# Sheet_1_2020-09-21_08-20-19.net
KiCad netlist of a schematic drawn in Altium Designer
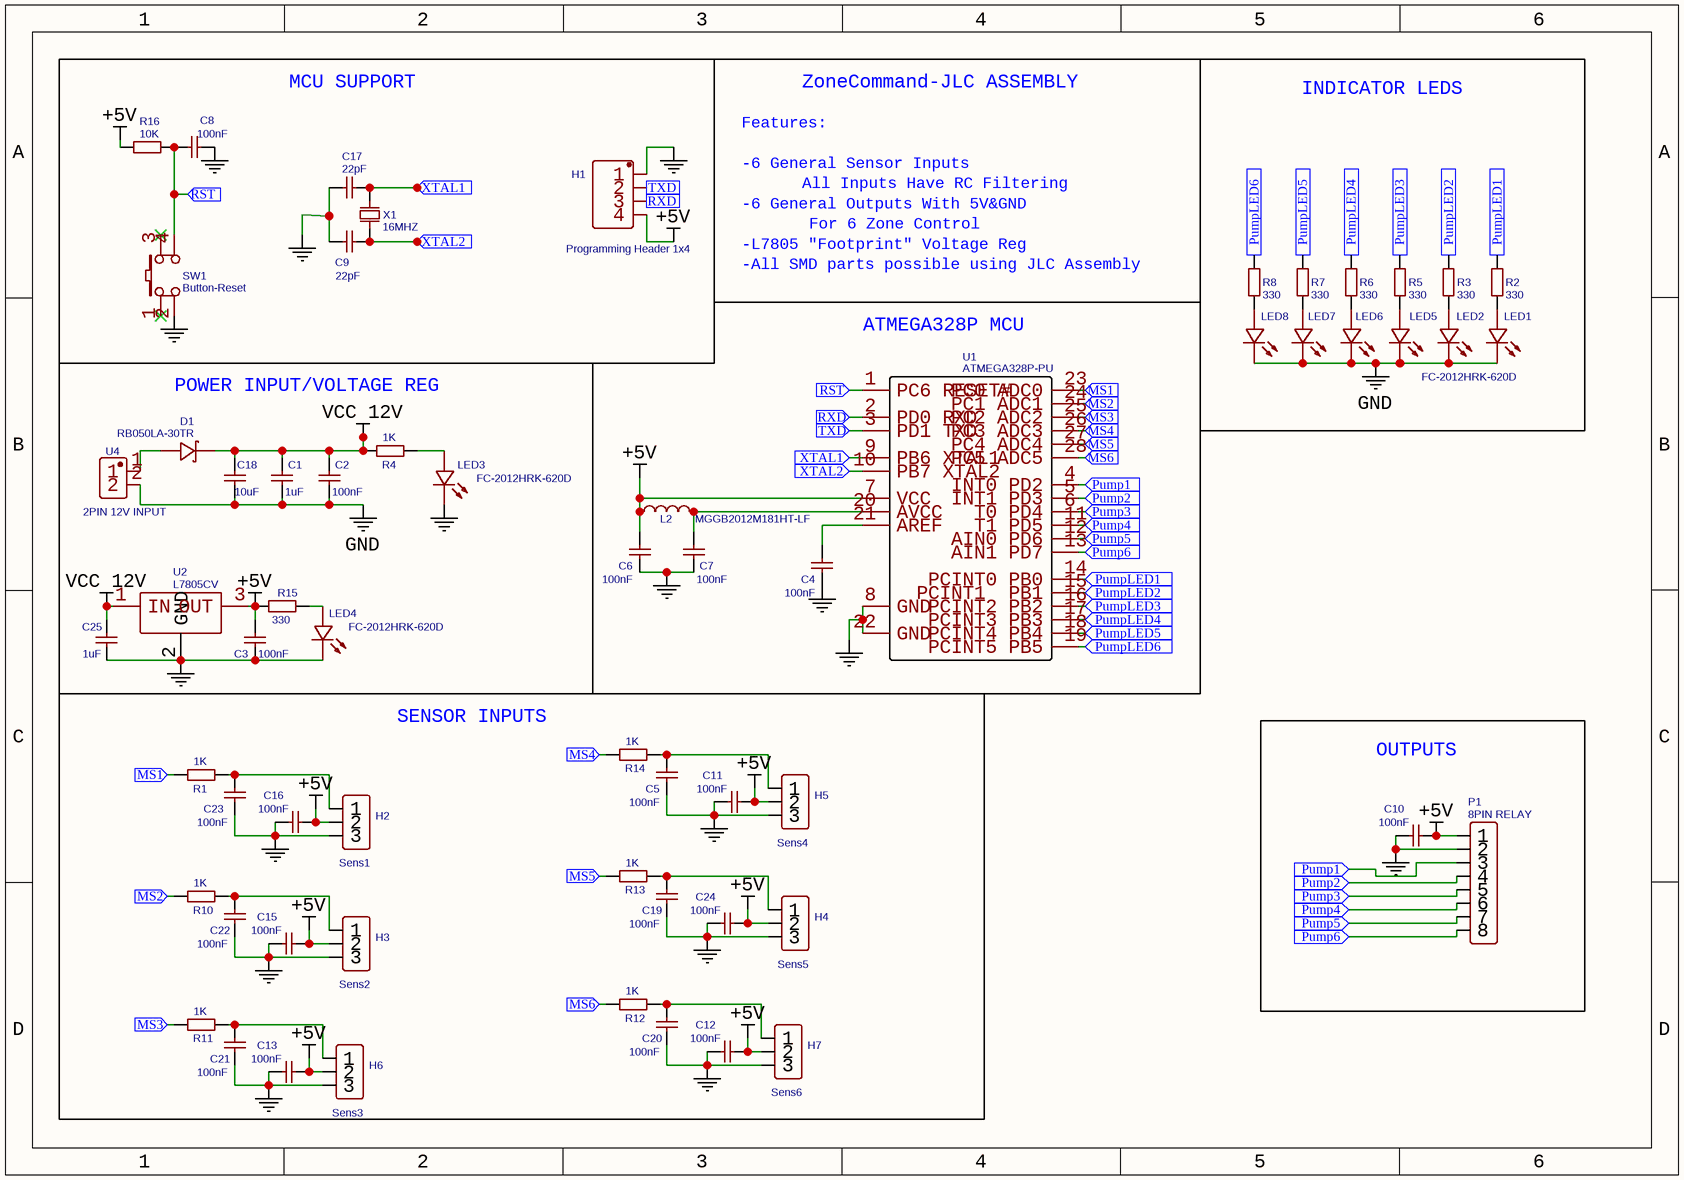
[diagram p0: Sheet_1_2020-09-21_08-20-19.schdoc]

(export (version "E")
  (design (tool "Eeschema 10.0.6"))
  (components
    (comp (ref "C1")
      (value "1uF")
      (fields
        (field (name "BOM_MANUFACTURER PART") "CL21B105KBFNNNE")
        (field (name "BOM_SUPPLIER PART") "C28323")
      )
      (libsource (lib "altium-import") (part "root_1_1uF_"))
    )
    (comp (ref "C2")
      (value "100nF")
      (fields
        (field (name "BOM_MANUFACTURER PART") "CC0805KRX7R9BB104")
        (field (name "BOM_SUPPLIER PART") "C49678")
      )
      (libsource (lib "altium-import") (part "root_3_100nF_"))
    )
    (comp (ref "C3")
      (value "100nF")
      (fields
        (field (name "BOM_MANUFACTURER PART") "CC0805KRX7R9BB104")
        (field (name "BOM_SUPPLIER PART") "C49678")
      )
      (libsource (lib "altium-import") (part "root_3_100nF_"))
    )
    (comp (ref "C4")
      (value "100nF")
      (fields
        (field (name "BOM_MANUFACTURER PART") "CC0805KRX7R9BB104")
        (field (name "BOM_SUPPLIER PART") "C49678")
      )
      (libsource (lib "altium-import") (part "root_3_100nF_"))
    )
    (comp (ref "C5")
      (value "100nF")
      (fields
        (field (name "BOM_MANUFACTURER PART") "CC0805KRX7R9BB104")
        (field (name "BOM_SUPPLIER PART") "C49678")
      )
      (libsource (lib "altium-import") (part "root_3_100nF_"))
    )
    (comp (ref "C6")
      (value "100nF")
      (fields
        (field (name "BOM_MANUFACTURER PART") "CC0805KRX7R9BB104")
        (field (name "BOM_SUPPLIER PART") "C49678")
      )
      (libsource (lib "altium-import") (part "root_3_100nF_"))
    )
    (comp (ref "C7")
      (value "100nF")
      (fields
        (field (name "BOM_MANUFACTURER PART") "CC0805KRX7R9BB104")
        (field (name "BOM_SUPPLIER PART") "C49678")
      )
      (libsource (lib "altium-import") (part "root_3_100nF_"))
    )
    (comp (ref "C8")
      (value "100nF")
      (fields
        (field (name "BOM_MANUFACTURER PART") "CC0805KRX7R9BB104")
        (field (name "BOM_SUPPLIER PART") "C49678")
      )
      (libsource (lib "altium-import") (part "root_0_100nF_"))
    )
    (comp (ref "C9")
      (value "22pF")
      (fields
        (field (name "BOM_MANUFACTURER PART") "CL21C220JBANNNC")
        (field (name "BOM_SUPPLIER PART") "C1804")
      )
      (libsource (lib "altium-import") (part "root_0_22pF_"))
    )
    (comp (ref "C10")
      (value "100nF")
      (fields
        (field (name "BOM_MANUFACTURER PART") "CC0805KRX7R9BB104")
        (field (name "BOM_SUPPLIER PART") "C49678")
      )
      (libsource (lib "altium-import") (part "root_0_100nF_"))
    )
    (comp (ref "C11")
      (value "100nF")
      (fields
        (field (name "BOM_MANUFACTURER PART") "CC0805KRX7R9BB104")
        (field (name "BOM_SUPPLIER PART") "C49678")
      )
      (libsource (lib "altium-import") (part "root_0_100nF_"))
    )
    (comp (ref "C12")
      (value "100nF")
      (fields
        (field (name "BOM_MANUFACTURER PART") "CC0805KRX7R9BB104")
        (field (name "BOM_SUPPLIER PART") "C49678")
      )
      (libsource (lib "altium-import") (part "root_0_100nF_"))
    )
    (comp (ref "C13")
      (value "100nF")
      (fields
        (field (name "BOM_MANUFACTURER PART") "CC0805KRX7R9BB104")
        (field (name "BOM_SUPPLIER PART") "C49678")
      )
      (libsource (lib "altium-import") (part "root_0_100nF_"))
    )
    (comp (ref "C15")
      (value "100nF")
      (fields
        (field (name "BOM_MANUFACTURER PART") "CC0805KRX7R9BB104")
        (field (name "BOM_SUPPLIER PART") "C49678")
      )
      (libsource (lib "altium-import") (part "root_0_100nF_"))
    )
    (comp (ref "C16")
      (value "100nF")
      (fields
        (field (name "BOM_MANUFACTURER PART") "CC0805KRX7R9BB104")
        (field (name "BOM_SUPPLIER PART") "C49678")
      )
      (libsource (lib "altium-import") (part "root_0_100nF_"))
    )
    (comp (ref "C17")
      (value "22pF")
      (fields
        (field (name "BOM_MANUFACTURER PART") "CL21C220JBANNNC")
        (field (name "BOM_SUPPLIER PART") "C1804")
      )
      (libsource (lib "altium-import") (part "root_0_22pF_"))
    )
    (comp (ref "C18")
      (value "10uF")
      (fields
        (field (name "BOM_MANUFACTURER PART") "CL21A106KAYNNNE")
        (field (name "BOM_SUPPLIER PART") "C15850")
      )
      (libsource (lib "altium-import") (part "root_3_10uF_"))
    )
    (comp (ref "C19")
      (value "100nF")
      (fields
        (field (name "BOM_MANUFACTURER PART") "CC0805KRX7R9BB104")
        (field (name "BOM_SUPPLIER PART") "C49678")
      )
      (libsource (lib "altium-import") (part "root_3_100nF_"))
    )
    (comp (ref "C20")
      (value "100nF")
      (fields
        (field (name "BOM_MANUFACTURER PART") "CC0805KRX7R9BB104")
        (field (name "BOM_SUPPLIER PART") "C49678")
      )
      (libsource (lib "altium-import") (part "root_3_100nF_"))
    )
    (comp (ref "C21")
      (value "100nF")
      (fields
        (field (name "BOM_MANUFACTURER PART") "CC0805KRX7R9BB104")
        (field (name "BOM_SUPPLIER PART") "C49678")
      )
      (libsource (lib "altium-import") (part "root_3_100nF_"))
    )
    (comp (ref "C22")
      (value "100nF")
      (fields
        (field (name "BOM_MANUFACTURER PART") "CC0805KRX7R9BB104")
        (field (name "BOM_SUPPLIER PART") "C49678")
      )
      (libsource (lib "altium-import") (part "root_3_100nF_"))
    )
    (comp (ref "C23")
      (value "100nF")
      (fields
        (field (name "BOM_MANUFACTURER PART") "CC0805KRX7R9BB104")
        (field (name "BOM_SUPPLIER PART") "C49678")
      )
      (libsource (lib "altium-import") (part "root_3_100nF_"))
    )
    (comp (ref "C24")
      (value "100nF")
      (fields
        (field (name "BOM_MANUFACTURER PART") "CC0805KRX7R9BB104")
        (field (name "BOM_SUPPLIER PART") "C49678")
      )
      (libsource (lib "altium-import") (part "root_0_100nF_"))
    )
    (comp (ref "C25")
      (value "1uF")
      (fields
        (field (name "BOM_MANUFACTURER PART") "CL21B105KBFNNNE")
        (field (name "BOM_SUPPLIER PART") "C28323")
      )
      (libsource (lib "altium-import") (part "root_1_1uF_"))
    )
    (comp (ref "D1")
      (value "RB050LA-30TR")
      (fields (field (name "BOM_SUPPLIER PART") "C162057") (field (name "CONTRIBUTOR") "LCSC"))
      (libsource (lib "altium-import") (part "root_0_RB050LA-30TR_"))
    )
    (comp (ref "H1")
      (value "Programming Header 1x4")
      (fields
        (field (name "BOM_MANUFACTURER PART") "210S-1*4P L=11.6MMGold-plated black")
        (field (name "BOM_SUPPLIER PART") "C124378")
        (field (name "CONTRIBUTOR") "LCSC")
      )
      (libsource (lib "altium-import") (part "root_0_Programming Header 1x4_"))
    )
    (comp (ref "H2")
      (value "Sens1")
      (fields
        (field (name "BOM_MANUFACTURER PART") "Header2.54mm 1*3P")
        (field (name "BOM_SUPPLIER PART") "C49257")
      )
      (libsource (lib "altium-import") (part "root_0_Sens1_"))
    )
    (comp (ref "H3")
      (value "Sens2")
      (fields
        (field (name "BOM_MANUFACTURER PART") "Header2.54mm 1*3P")
        (field (name "BOM_SUPPLIER PART") "C49257")
      )
      (libsource (lib "altium-import") (part "root_0_Sens2_"))
    )
    (comp (ref "H4")
      (value "Sens5")
      (fields
        (field (name "BOM_MANUFACTURER PART") "Header2.54mm 1*3P")
        (field (name "BOM_SUPPLIER PART") "C49257")
      )
      (libsource (lib "altium-import") (part "root_0_Sens5_"))
    )
    (comp (ref "H5")
      (value "Sens4")
      (fields
        (field (name "BOM_MANUFACTURER PART") "Header2.54mm 1*3P")
        (field (name "BOM_SUPPLIER PART") "C49257")
      )
      (libsource (lib "altium-import") (part "root_0_Sens4_"))
    )
    (comp (ref "H6")
      (value "Sens3")
      (fields
        (field (name "BOM_MANUFACTURER PART") "Header2.54mm 1*3P")
        (field (name "BOM_SUPPLIER PART") "C49257")
      )
      (libsource (lib "altium-import") (part "root_0_Sens3_"))
    )
    (comp (ref "H7")
      (value "Sens6")
      (fields
        (field (name "BOM_MANUFACTURER PART") "Header2.54mm 1*3P")
        (field (name "BOM_SUPPLIER PART") "C49257")
      )
      (libsource (lib "altium-import") (part "root_0_Sens6_"))
    )
    (comp (ref "L2")
      (value "MGGB2012M181HT-LF")
      (fields (field (name "BOM_SUPPLIER PART") "C486339") (field (name "CONTRIBUTOR") "LCSC"))
      (libsource (lib "altium-import") (part "root_0_MGGB2012M181HT-LF_"))
    )
    (comp (ref "LED1")
      (value "FC-2012HRK-620D")
      (fields (field (name "BOM_SUPPLIER PART") "C84256"))
      (libsource (lib "altium-import") (part "root_1_FC-2012HRK-620D_"))
    )
    (comp (ref "LED2")
      (value "FC-2012HRK-620D")
      (fields (field (name "BOM_SUPPLIER PART") "C84256"))
      (libsource (lib "altium-import") (part "root_1_FC-2012HRK-620D_"))
    )
    (comp (ref "LED3")
      (value "FC-2012HRK-620D")
      (fields (field (name "BOM_SUPPLIER PART") "C84256"))
      (libsource (lib "altium-import") (part "root_1_FC-2012HRK-620D_"))
    )
    (comp (ref "LED4")
      (value "FC-2012HRK-620D")
      (fields (field (name "BOM_SUPPLIER PART") "C84256"))
      (libsource (lib "altium-import") (part "root_1_FC-2012HRK-620D_"))
    )
    (comp (ref "LED5")
      (value "FC-2012HRK-620D")
      (fields (field (name "BOM_SUPPLIER PART") "C84256"))
      (libsource (lib "altium-import") (part "root_1_FC-2012HRK-620D_"))
    )
    (comp (ref "LED6")
      (value "FC-2012HRK-620D")
      (fields (field (name "BOM_SUPPLIER PART") "C84256"))
      (libsource (lib "altium-import") (part "root_1_FC-2012HRK-620D_"))
    )
    (comp (ref "LED7")
      (value "FC-2012HRK-620D")
      (fields (field (name "BOM_SUPPLIER PART") "C84256"))
      (libsource (lib "altium-import") (part "root_1_FC-2012HRK-620D_"))
    )
    (comp (ref "LED8")
      (value "FC-2012HRK-620D")
      (fields (field (name "BOM_SUPPLIER PART") "C84256"))
      (libsource (lib "altium-import") (part "root_1_FC-2012HRK-620D_"))
    )
    (comp (ref "P1")
      (value "8PIN RELAY")
      (fields
        (field (name "BOM_MANUFACTURER PART") "Female headerHDR1X8-2.54")
        (field (name "BOM_SUPPLIER PART") "C27438")
      )
      (libsource (lib "altium-import") (part "root_0_8PIN RELAY_"))
    )
    (comp (ref "R1")
      (value "1K")
      (fields
        (field (name "BOM_MANUFACTURER PART") "0805W8F1001T5E")
        (field (name "BOM_SUPPLIER PART") "C17513")
      )
      (libsource (lib "altium-import") (part "root_0_1K_"))
    )
    (comp (ref "R2")
      (value "330")
      (fields
        (field (name "BOM_MANUFACTURER PART") "0805W8F3300T5E")
        (field (name "BOM_SUPPLIER PART") "C17630")
      )
      (libsource (lib "altium-import") (part "root_1_330_"))
    )
    (comp (ref "R3")
      (value "330")
      (fields
        (field (name "BOM_MANUFACTURER PART") "0805W8F3300T5E")
        (field (name "BOM_SUPPLIER PART") "C17630")
      )
      (libsource (lib "altium-import") (part "root_1_330_"))
    )
    (comp (ref "R4")
      (value "1K")
      (fields
        (field (name "BOM_MANUFACTURER PART") "0805W8F1001T5E")
        (field (name "BOM_SUPPLIER PART") "C17513")
      )
      (libsource (lib "altium-import") (part "root_0_1K_"))
    )
    (comp (ref "R5")
      (value "330")
      (fields
        (field (name "BOM_MANUFACTURER PART") "0805W8F3300T5E")
        (field (name "BOM_SUPPLIER PART") "C17630")
      )
      (libsource (lib "altium-import") (part "root_1_330_"))
    )
    (comp (ref "R6")
      (value "330")
      (fields
        (field (name "BOM_MANUFACTURER PART") "0805W8F3300T5E")
        (field (name "BOM_SUPPLIER PART") "C17630")
      )
      (libsource (lib "altium-import") (part "root_1_330_"))
    )
    (comp (ref "R7")
      (value "330")
      (fields
        (field (name "BOM_MANUFACTURER PART") "0805W8F3300T5E")
        (field (name "BOM_SUPPLIER PART") "C17630")
      )
      (libsource (lib "altium-import") (part "root_1_330_"))
    )
    (comp (ref "R8")
      (value "330")
      (fields
        (field (name "BOM_MANUFACTURER PART") "0805W8F3300T5E")
        (field (name "BOM_SUPPLIER PART") "C17630")
      )
      (libsource (lib "altium-import") (part "root_1_330_"))
    )
    (comp (ref "R10")
      (value "1K")
      (fields
        (field (name "BOM_MANUFACTURER PART") "0805W8F1001T5E")
        (field (name "BOM_SUPPLIER PART") "C17513")
      )
      (libsource (lib "altium-import") (part "root_0_1K_"))
    )
    (comp (ref "R11")
      (value "1K")
      (fields
        (field (name "BOM_MANUFACTURER PART") "0805W8F1001T5E")
        (field (name "BOM_SUPPLIER PART") "C17513")
      )
      (libsource (lib "altium-import") (part "root_0_1K_"))
    )
    (comp (ref "R12")
      (value "1K")
      (fields
        (field (name "BOM_MANUFACTURER PART") "0805W8F1001T5E")
        (field (name "BOM_SUPPLIER PART") "C17513")
      )
      (libsource (lib "altium-import") (part "root_0_1K_"))
    )
    (comp (ref "R13")
      (value "1K")
      (fields
        (field (name "BOM_MANUFACTURER PART") "0805W8F1001T5E")
        (field (name "BOM_SUPPLIER PART") "C17513")
      )
      (libsource (lib "altium-import") (part "root_0_1K_"))
    )
    (comp (ref "R14")
      (value "1K")
      (fields
        (field (name "BOM_MANUFACTURER PART") "0805W8F1001T5E")
        (field (name "BOM_SUPPLIER PART") "C17513")
      )
      (libsource (lib "altium-import") (part "root_0_1K_"))
    )
    (comp (ref "R15")
      (value "330")
      (fields
        (field (name "BOM_MANUFACTURER PART") "0805W8F3300T5E")
        (field (name "BOM_SUPPLIER PART") "C17630")
      )
      (libsource (lib "altium-import") (part "root_0_330_"))
    )
    (comp (ref "R16")
      (value "10K")
      (fields
        (field (name "BOM_MANUFACTURER PART") "0805W8F1002T5E")
        (field (name "BOM_SUPPLIER PART") "C17414")
      )
      (libsource (lib "altium-import") (part "root_0_10K_"))
    )
    (comp (ref "SW1")
      (value "Button-Reset")
      (fields
        (field (name "BOM_SUPPLIER PART") "C71836")
        (field (name "BOM_MANUFACTURER PART") "Switch,6*6*6Plastic head,260G, 0.25mm,Straight line")
      )
      (libsource (lib "altium-import") (part "root_1_Button-Reset_"))
    )
    (comp (ref "U1")
      (value "ATMEGA328P-PU")
      (fields (field (name "BOM_SUPPLIER PART") "C33901") (field (name "CONTRIBUTOR") "LCSC"))
      (libsource (lib "altium-import") (part "root_0_ATMEGA328P-PU_"))
    )
    (comp (ref "U2")
      (value "L7805CV")
      (fields (field (name "BOM_SUPPLIER PART") "C111887"))
      (libsource (lib "altium-import") (part "root_0_L7805CV_"))
    )
    (comp (ref "U4")
      (value "2PIN 12V INPUT")
      (fields
        (field (name "BOM_SUPPLIER PART") "C691859")
        (field (name "BOM_MANUFACTURER PART") "DG500-5.08-02P-14-00A(H)")
        (field (name "CONTRIBUTOR") "LCSC")
      )
      (libsource (lib "altium-import") (part "root_0_2PIN 12V INPUT_"))
    )
    (comp (ref "X1")
      (value "16MHZ")
      (fields
        (field (name "BOM_SUPPLIER PART") "C389708")
        (field (name "BOM_MANUFACTURER PART") "5S0-1600A1620-00")
        (field (name "CONTRIBUTOR") "LCSC")
      )
      (libsource (lib "altium-import") (part "root_3_16MHZ_"))
    )
  )
  (nets
    (net (code "1") (name "+5V") (class "Default")
      (node (ref "C10") (pin "2") (pinfunction "2_2") (pintype "passive"))
      (node (ref "C11") (pin "2") (pinfunction "2_2") (pintype "passive"))
      (node (ref "C12") (pin "2") (pinfunction "2_2") (pintype "passive"))
      (node (ref "C13") (pin "2") (pinfunction "2_2") (pintype "passive"))
      (node (ref "C15") (pin "2") (pinfunction "2_2") (pintype "passive"))
      (node (ref "C16") (pin "2") (pinfunction "2_2") (pintype "passive"))
      (node (ref "C24") (pin "2") (pinfunction "2_2") (pintype "passive"))
      (node (ref "C3") (pin "1") (pinfunction "1_1") (pintype "passive"))
      (node (ref "C6") (pin "1") (pinfunction "1_1") (pintype "passive"))
      (node (ref "H1") (pin "4") (pinfunction "4_4") (pintype "passive"))
      (node (ref "H2") (pin "2") (pinfunction "2_2") (pintype "passive"))
      (node (ref "H3") (pin "2") (pinfunction "2_2") (pintype "passive"))
      (node (ref "H4") (pin "2") (pinfunction "2_2") (pintype "passive"))
      (node (ref "H5") (pin "2") (pinfunction "2_2") (pintype "passive"))
      (node (ref "H6") (pin "2") (pinfunction "2_2") (pintype "passive"))
      (node (ref "H7") (pin "2") (pinfunction "2_2") (pintype "passive"))
      (node (ref "L2") (pin "1") (pinfunction "1_1") (pintype "passive"))
      (node (ref "P1") (pin "1") (pinfunction "1_1") (pintype "passive"))
      (node (ref "R15") (pin "1") (pinfunction "1_1") (pintype "passive"))
      (node (ref "R16") (pin "1") (pinfunction "1_1") (pintype "passive"))
      (node (ref "U1") (pin "7") (pinfunction "VCC_7") (pintype "passive"))
      (node (ref "U2") (pin "3") (pinfunction "OUT_3") (pintype "passive"))
    )
    (net (code "2") (name "/MS1") (class "Default")
      (node (ref "R1") (pin "1") (pinfunction "1_1") (pintype "passive"))
      (node (ref "U1") (pin "23") (pinfunction "PC0_ADC0_23") (pintype "passive"))
    )
    (net (code "3") (name "/MS2") (class "Default")
      (node (ref "R10") (pin "1") (pinfunction "1_1") (pintype "passive"))
      (node (ref "U1") (pin "24") (pinfunction "PC1_ADC1_24") (pintype "passive"))
    )
    (net (code "4") (name "/MS3") (class "Default")
      (node (ref "R11") (pin "1") (pinfunction "1_1") (pintype "passive"))
      (node (ref "U1") (pin "25") (pinfunction "PC2_ADC2_25") (pintype "passive"))
    )
    (net (code "5") (name "/MS4") (class "Default")
      (node (ref "R14") (pin "1") (pinfunction "1_1") (pintype "passive"))
      (node (ref "U1") (pin "26") (pinfunction "PC3_ADC3_26") (pintype "passive"))
    )
    (net (code "6") (name "/MS5") (class "Default")
      (node (ref "R13") (pin "1") (pinfunction "1_1") (pintype "passive"))
      (node (ref "U1") (pin "27") (pinfunction "PC4_ADC4_27") (pintype "passive"))
    )
    (net (code "7") (name "/MS6") (class "Default")
      (node (ref "R12") (pin "1") (pinfunction "1_1") (pintype "passive"))
      (node (ref "U1") (pin "28") (pinfunction "PC5_ADC5_28") (pintype "passive"))
    )
    (net (code "8") (name "/Pump1") (class "Default")
      (node (ref "P1") (pin "3") (pinfunction "3_3") (pintype "passive"))
      (node (ref "U1") (pin "4") (pinfunction "INT0_PD2_4") (pintype "passive"))
    )
    (net (code "9") (name "/Pump2") (class "Default")
      (node (ref "P1") (pin "4") (pinfunction "4_4") (pintype "passive"))
      (node (ref "U1") (pin "5") (pinfunction "INT1_PD3_5") (pintype "passive"))
    )
    (net (code "10") (name "/Pump3") (class "Default")
      (node (ref "P1") (pin "5") (pinfunction "5_5") (pintype "passive"))
      (node (ref "U1") (pin "6") (pinfunction "T0_PD4_6") (pintype "passive"))
    )
    (net (code "11") (name "/Pump4") (class "Default")
      (node (ref "P1") (pin "6") (pinfunction "6_6") (pintype "passive"))
      (node (ref "U1") (pin "11") (pinfunction "T1_PD5_11") (pintype "passive"))
    )
    (net (code "12") (name "/Pump5") (class "Default")
      (node (ref "P1") (pin "7") (pinfunction "7_7") (pintype "passive"))
      (node (ref "U1") (pin "12") (pinfunction "AIN0_PD6_12") (pintype "passive"))
    )
    (net (code "13") (name "/Pump6") (class "Default")
      (node (ref "P1") (pin "8") (pinfunction "8_8") (pintype "passive"))
      (node (ref "U1") (pin "13") (pinfunction "AIN1_PD7_13") (pintype "passive"))
    )
    (net (code "14") (name "/PumpLED1") (class "Default")
      (node (ref "R2") (pin "2") (pinfunction "2_2") (pintype "passive"))
      (node (ref "U1") (pin "14") (pinfunction "PCINT0_PB0_14") (pintype "passive"))
    )
    (net (code "15") (name "/PumpLED2") (class "Default")
      (node (ref "R3") (pin "2") (pinfunction "2_2") (pintype "passive"))
      (node (ref "U1") (pin "15") (pinfunction "PCINT1__PB1_15") (pintype "passive"))
    )
    (net (code "16") (name "/PumpLED3") (class "Default")
      (node (ref "R5") (pin "2") (pinfunction "2_2") (pintype "passive"))
      (node (ref "U1") (pin "16") (pinfunction "PCINT2_PB2_16") (pintype "passive"))
    )
    (net (code "17") (name "/PumpLED4") (class "Default")
      (node (ref "R6") (pin "2") (pinfunction "2_2") (pintype "passive"))
      (node (ref "U1") (pin "17") (pinfunction "PCINT3_PB3_17") (pintype "passive"))
    )
    (net (code "18") (name "/PumpLED5") (class "Default")
      (node (ref "R7") (pin "2") (pinfunction "2_2") (pintype "passive"))
      (node (ref "U1") (pin "18") (pinfunction "PCINT4_PB4_18") (pintype "passive"))
    )
    (net (code "19") (name "/PumpLED6") (class "Default")
      (node (ref "R8") (pin "2") (pinfunction "2_2") (pintype "passive"))
      (node (ref "U1") (pin "19") (pinfunction "PCINT5_PB5_19") (pintype "passive"))
    )
    (net (code "20") (name "/RST") (class "Default")
      (node (ref "C8") (pin "1") (pinfunction "1_1") (pintype "passive"))
      (node (ref "R16") (pin "2") (pinfunction "2_2") (pintype "passive"))
      (node (ref "SW1") (pin "4") (pinfunction "4_4") (pintype "passive"))
      (node (ref "U1") (pin "1") (pinfunction "PC6_RESET#_1") (pintype "passive"))
    )
    (net (code "21") (name "/RXD") (class "Default")
      (node (ref "H1") (pin "3") (pinfunction "3_3") (pintype "passive"))
      (node (ref "U1") (pin "2") (pinfunction "PD0_RXD_2") (pintype "passive"))
    )
    (net (code "22") (name "/TXD") (class "Default")
      (node (ref "H1") (pin "2") (pinfunction "2_2") (pintype "passive"))
      (node (ref "U1") (pin "3") (pinfunction "PD1_TXD_3") (pintype "passive"))
    )
    (net (code "23") (name "/XTAL1") (class "Default")
      (node (ref "C17") (pin "2") (pinfunction "2_2") (pintype "passive"))
      (node (ref "U1") (pin "9") (pinfunction "PB6_XTAL1_9") (pintype "passive"))
      (node (ref "X1") (pin "1") (pinfunction "OSC1_1") (pintype "passive"))
    )
    (net (code "24") (name "/XTAL2") (class "Default")
      (node (ref "C9") (pin "2") (pinfunction "2_2") (pintype "passive"))
      (node (ref "U1") (pin "10") (pinfunction "PB7_XTAL2_10") (pintype "passive"))
      (node (ref "X1") (pin "2") (pinfunction "OSC2_2") (pintype "passive"))
    )
    (net (code "25") (name "GND") (class "Default")
      (node (ref "C1") (pin "1") (pinfunction "1_1") (pintype "passive"))
      (node (ref "C10") (pin "1") (pinfunction "1_1") (pintype "passive"))
      (node (ref "C11") (pin "1") (pinfunction "1_1") (pintype "passive"))
      (node (ref "C12") (pin "1") (pinfunction "1_1") (pintype "passive"))
      (node (ref "C13") (pin "1") (pinfunction "1_1") (pintype "passive"))
      (node (ref "C15") (pin "1") (pinfunction "1_1") (pintype "passive"))
      (node (ref "C16") (pin "1") (pinfunction "1_1") (pintype "passive"))
      (node (ref "C17") (pin "1") (pinfunction "1_1") (pintype "passive"))
      (node (ref "C18") (pin "2") (pinfunction "2_2") (pintype "passive"))
      (node (ref "C19") (pin "2") (pinfunction "2_2") (pintype "passive"))
      (node (ref "C2") (pin "2") (pinfunction "2_2") (pintype "passive"))
      (node (ref "C20") (pin "2") (pinfunction "2_2") (pintype "passive"))
      (node (ref "C21") (pin "2") (pinfunction "2_2") (pintype "passive"))
      (node (ref "C22") (pin "2") (pinfunction "2_2") (pintype "passive"))
      (node (ref "C23") (pin "2") (pinfunction "2_2") (pintype "passive"))
      (node (ref "C24") (pin "1") (pinfunction "1_1") (pintype "passive"))
      (node (ref "C25") (pin "1") (pinfunction "1_1") (pintype "passive"))
      (node (ref "C3") (pin "2") (pinfunction "2_2") (pintype "passive"))
      (node (ref "C4") (pin "2") (pinfunction "2_2") (pintype "passive"))
      (node (ref "C5") (pin "2") (pinfunction "2_2") (pintype "passive"))
      (node (ref "C6") (pin "2") (pinfunction "2_2") (pintype "passive"))
      (node (ref "C7") (pin "2") (pinfunction "2_2") (pintype "passive"))
      (node (ref "C8") (pin "2") (pinfunction "2_2") (pintype "passive"))
      (node (ref "C9") (pin "1") (pinfunction "1_1") (pintype "passive"))
      (node (ref "H1") (pin "1") (pinfunction "1_1") (pintype "passive"))
      (node (ref "H2") (pin "3") (pinfunction "3_3") (pintype "passive"))
      (node (ref "H3") (pin "3") (pinfunction "3_3") (pintype "passive"))
      (node (ref "H4") (pin "3") (pinfunction "3_3") (pintype "passive"))
      (node (ref "H5") (pin "3") (pinfunction "3_3") (pintype "passive"))
      (node (ref "H6") (pin "3") (pinfunction "3_3") (pintype "passive"))
      (node (ref "H7") (pin "3") (pinfunction "3_3") (pintype "passive"))
      (node (ref "LED1") (pin "1") (pinfunction "-_1") (pintype "passive"))
      (node (ref "LED2") (pin "1") (pinfunction "-_1") (pintype "passive"))
      (node (ref "LED3") (pin "1") (pinfunction "-_1") (pintype "passive"))
      (node (ref "LED4") (pin "1") (pinfunction "-_1") (pintype "passive"))
      (node (ref "LED5") (pin "1") (pinfunction "-_1") (pintype "passive"))
      (node (ref "LED6") (pin "1") (pinfunction "-_1") (pintype "passive"))
      (node (ref "LED7") (pin "1") (pinfunction "-_1") (pintype "passive"))
      (node (ref "LED8") (pin "1") (pinfunction "-_1") (pintype "passive"))
      (node (ref "P1") (pin "2") (pinfunction "2_2") (pintype "passive"))
      (node (ref "SW1") (pin "2") (pinfunction "2_2") (pintype "passive"))
      (node (ref "U1") (pin "22") (pinfunction "GND_22") (pintype "passive"))
      (node (ref "U1") (pin "8") (pinfunction "GND_8") (pintype "passive"))
      (node (ref "U2") (pin "2") (pinfunction "GND_2") (pintype "passive"))
      (node (ref "U4") (pin "2") (pinfunction "2_2") (pintype "passive"))
    )
    (net (code "26") (name "Net-(C5-Pad1)") (class "Default")
      (node (ref "C5") (pin "1") (pinfunction "1_1") (pintype "passive"))
      (node (ref "H5") (pin "1") (pinfunction "1_1") (pintype "passive"))
      (node (ref "R14") (pin "2") (pinfunction "2_2") (pintype "passive"))
    )
    (net (code "27") (name "Net-(C19-Pad1)") (class "Default")
      (node (ref "C19") (pin "1") (pinfunction "1_1") (pintype "passive"))
      (node (ref "H4") (pin "1") (pinfunction "1_1") (pintype "passive"))
      (node (ref "R13") (pin "2") (pinfunction "2_2") (pintype "passive"))
    )
    (net (code "28") (name "Net-(C20-Pad1)") (class "Default")
      (node (ref "C20") (pin "1") (pinfunction "1_1") (pintype "passive"))
      (node (ref "H7") (pin "1") (pinfunction "1_1") (pintype "passive"))
      (node (ref "R12") (pin "2") (pinfunction "2_2") (pintype "passive"))
    )
    (net (code "29") (name "Net-(C21-Pad1)") (class "Default")
      (node (ref "C21") (pin "1") (pinfunction "1_1") (pintype "passive"))
      (node (ref "H6") (pin "1") (pinfunction "1_1") (pintype "passive"))
      (node (ref "R11") (pin "2") (pinfunction "2_2") (pintype "passive"))
    )
    (net (code "30") (name "Net-(C22-Pad1)") (class "Default")
      (node (ref "C22") (pin "1") (pinfunction "1_1") (pintype "passive"))
      (node (ref "H3") (pin "1") (pinfunction "1_1") (pintype "passive"))
      (node (ref "R10") (pin "2") (pinfunction "2_2") (pintype "passive"))
    )
    (net (code "31") (name "Net-(C23-Pad1)") (class "Default")
      (node (ref "C23") (pin "1") (pinfunction "1_1") (pintype "passive"))
      (node (ref "H2") (pin "1") (pinfunction "1_1") (pintype "passive"))
      (node (ref "R1") (pin "2") (pinfunction "2_2") (pintype "passive"))
    )
    (net (code "32") (name "Net-(D1-A)") (class "Default")
      (node (ref "D1") (pin "2") (pinfunction "A_2") (pintype "passive"))
      (node (ref "U4") (pin "1") (pinfunction "1_1") (pintype "passive"))
    )
    (net (code "33") (name "Net-(LED1-+)") (class "Default")
      (node (ref "LED1") (pin "2") (pinfunction "+_2") (pintype "passive"))
      (node (ref "R2") (pin "1") (pinfunction "1_1") (pintype "passive"))
    )
    (net (code "34") (name "Net-(LED2-+)") (class "Default")
      (node (ref "LED2") (pin "2") (pinfunction "+_2") (pintype "passive"))
      (node (ref "R3") (pin "1") (pinfunction "1_1") (pintype "passive"))
    )
    (net (code "35") (name "Net-(LED3-+)") (class "Default")
      (node (ref "LED3") (pin "2") (pinfunction "+_2") (pintype "passive"))
      (node (ref "R4") (pin "2") (pinfunction "2_2") (pintype "passive"))
    )
    (net (code "36") (name "Net-(LED4-+)") (class "Default")
      (node (ref "LED4") (pin "2") (pinfunction "+_2") (pintype "passive"))
      (node (ref "R15") (pin "2") (pinfunction "2_2") (pintype "passive"))
    )
    (net (code "37") (name "Net-(LED5-+)") (class "Default")
      (node (ref "LED5") (pin "2") (pinfunction "+_2") (pintype "passive"))
      (node (ref "R5") (pin "1") (pinfunction "1_1") (pintype "passive"))
    )
    (net (code "38") (name "Net-(LED6-+)") (class "Default")
      (node (ref "LED6") (pin "2") (pinfunction "+_2") (pintype "passive"))
      (node (ref "R6") (pin "1") (pinfunction "1_1") (pintype "passive"))
    )
    (net (code "39") (name "Net-(LED7-+)") (class "Default")
      (node (ref "LED7") (pin "2") (pinfunction "+_2") (pintype "passive"))
      (node (ref "R7") (pin "1") (pinfunction "1_1") (pintype "passive"))
    )
    (net (code "40") (name "Net-(LED8-+)") (class "Default")
      (node (ref "LED8") (pin "2") (pinfunction "+_2") (pintype "passive"))
      (node (ref "R8") (pin "1") (pinfunction "1_1") (pintype "passive"))
    )
    (net (code "41") (name "Net-(U1-AREF)") (class "Default")
      (node (ref "C4") (pin "1") (pinfunction "1_1") (pintype "passive"))
      (node (ref "U1") (pin "21") (pinfunction "AREF_21") (pintype "passive"))
    )
    (net (code "42") (name "Net-(U1-AVCC)") (class "Default")
      (node (ref "C7") (pin "1") (pinfunction "1_1") (pintype "passive"))
      (node (ref "L2") (pin "2") (pinfunction "2_2") (pintype "passive"))
      (node (ref "U1") (pin "20") (pinfunction "AVCC_20") (pintype "passive"))
    )
    (net (code "43") (name "VCC 12V") (class "Default")
      (node (ref "C1") (pin "2") (pinfunction "2_2") (pintype "passive"))
      (node (ref "C18") (pin "1") (pinfunction "1_1") (pintype "passive"))
      (node (ref "C2") (pin "1") (pinfunction "1_1") (pintype "passive"))
      (node (ref "C25") (pin "2") (pinfunction "2_2") (pintype "passive"))
      (node (ref "D1") (pin "1") (pinfunction "K_1") (pintype "passive"))
      (node (ref "R4") (pin "1") (pinfunction "1_1") (pintype "passive"))
      (node (ref "U2") (pin "1") (pinfunction "IN_1") (pintype "passive"))
    )
    (net (code "44") (name "unconnected-(SW1-Pad1)") (class "Default")
      (node (ref "SW1") (pin "1") (pinfunction "1_1") (pintype "passive+no_connect"))
    )
    (net (code "45") (name "unconnected-(SW1-Pad3)") (class "Default")
      (node (ref "SW1") (pin "3") (pinfunction "3_3") (pintype "passive+no_connect"))
    )
  )
)
